# airball_sensor_board_v7.net
KiCad netlist of a schematic drawn in EAGLE
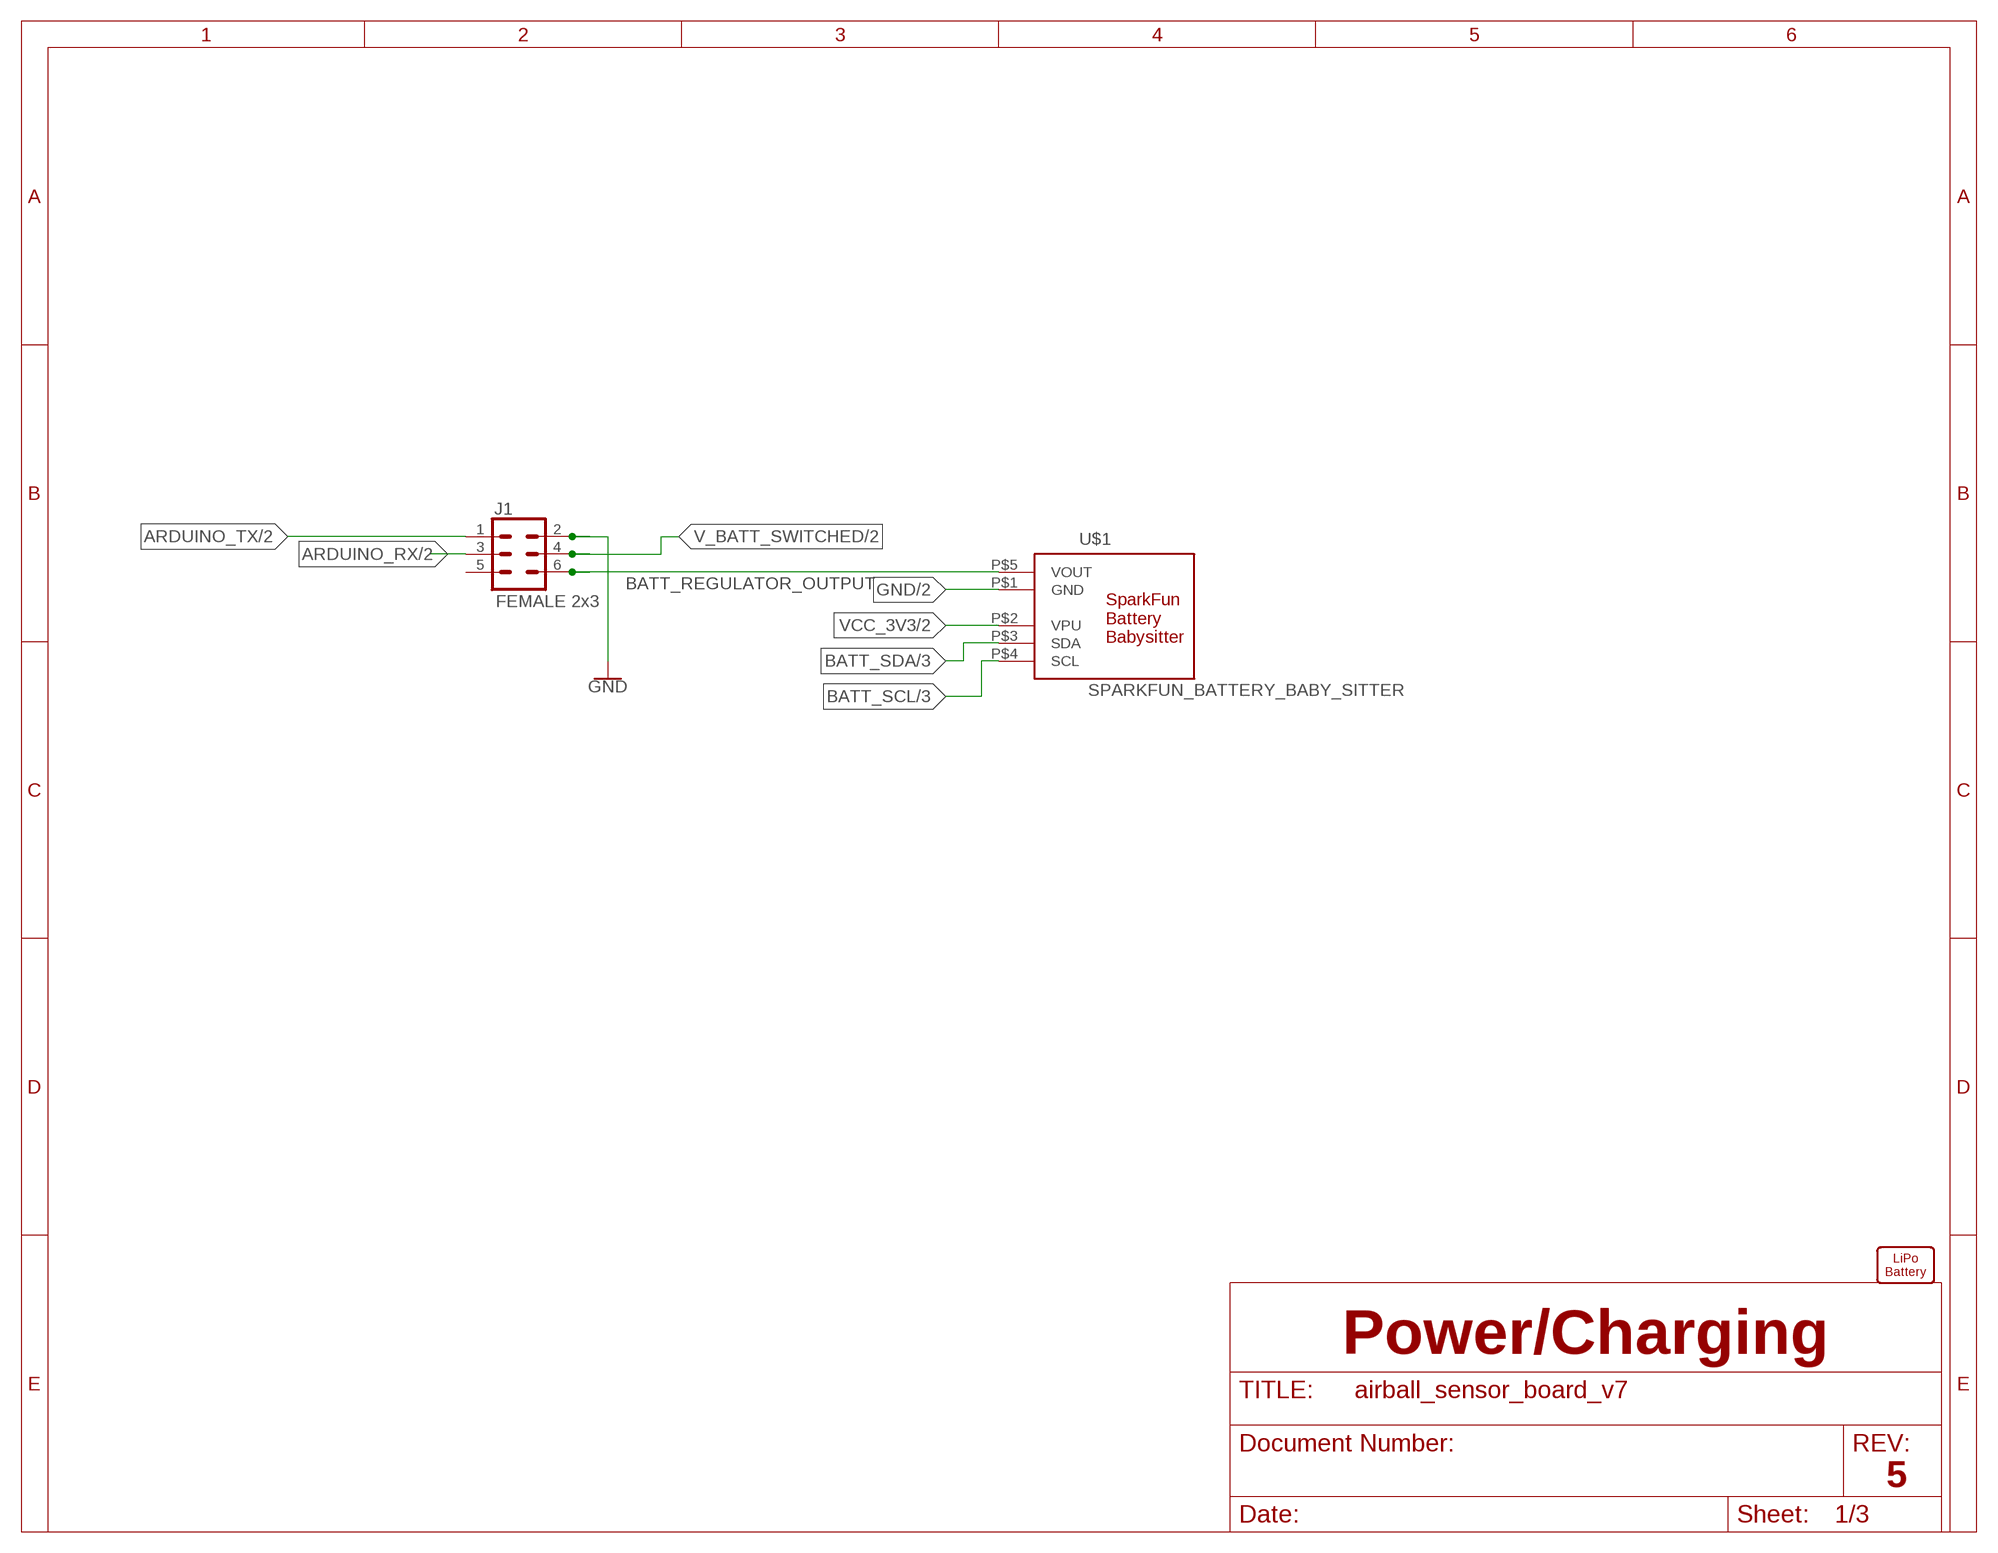
[diagram p0: schematic, sheet 1]
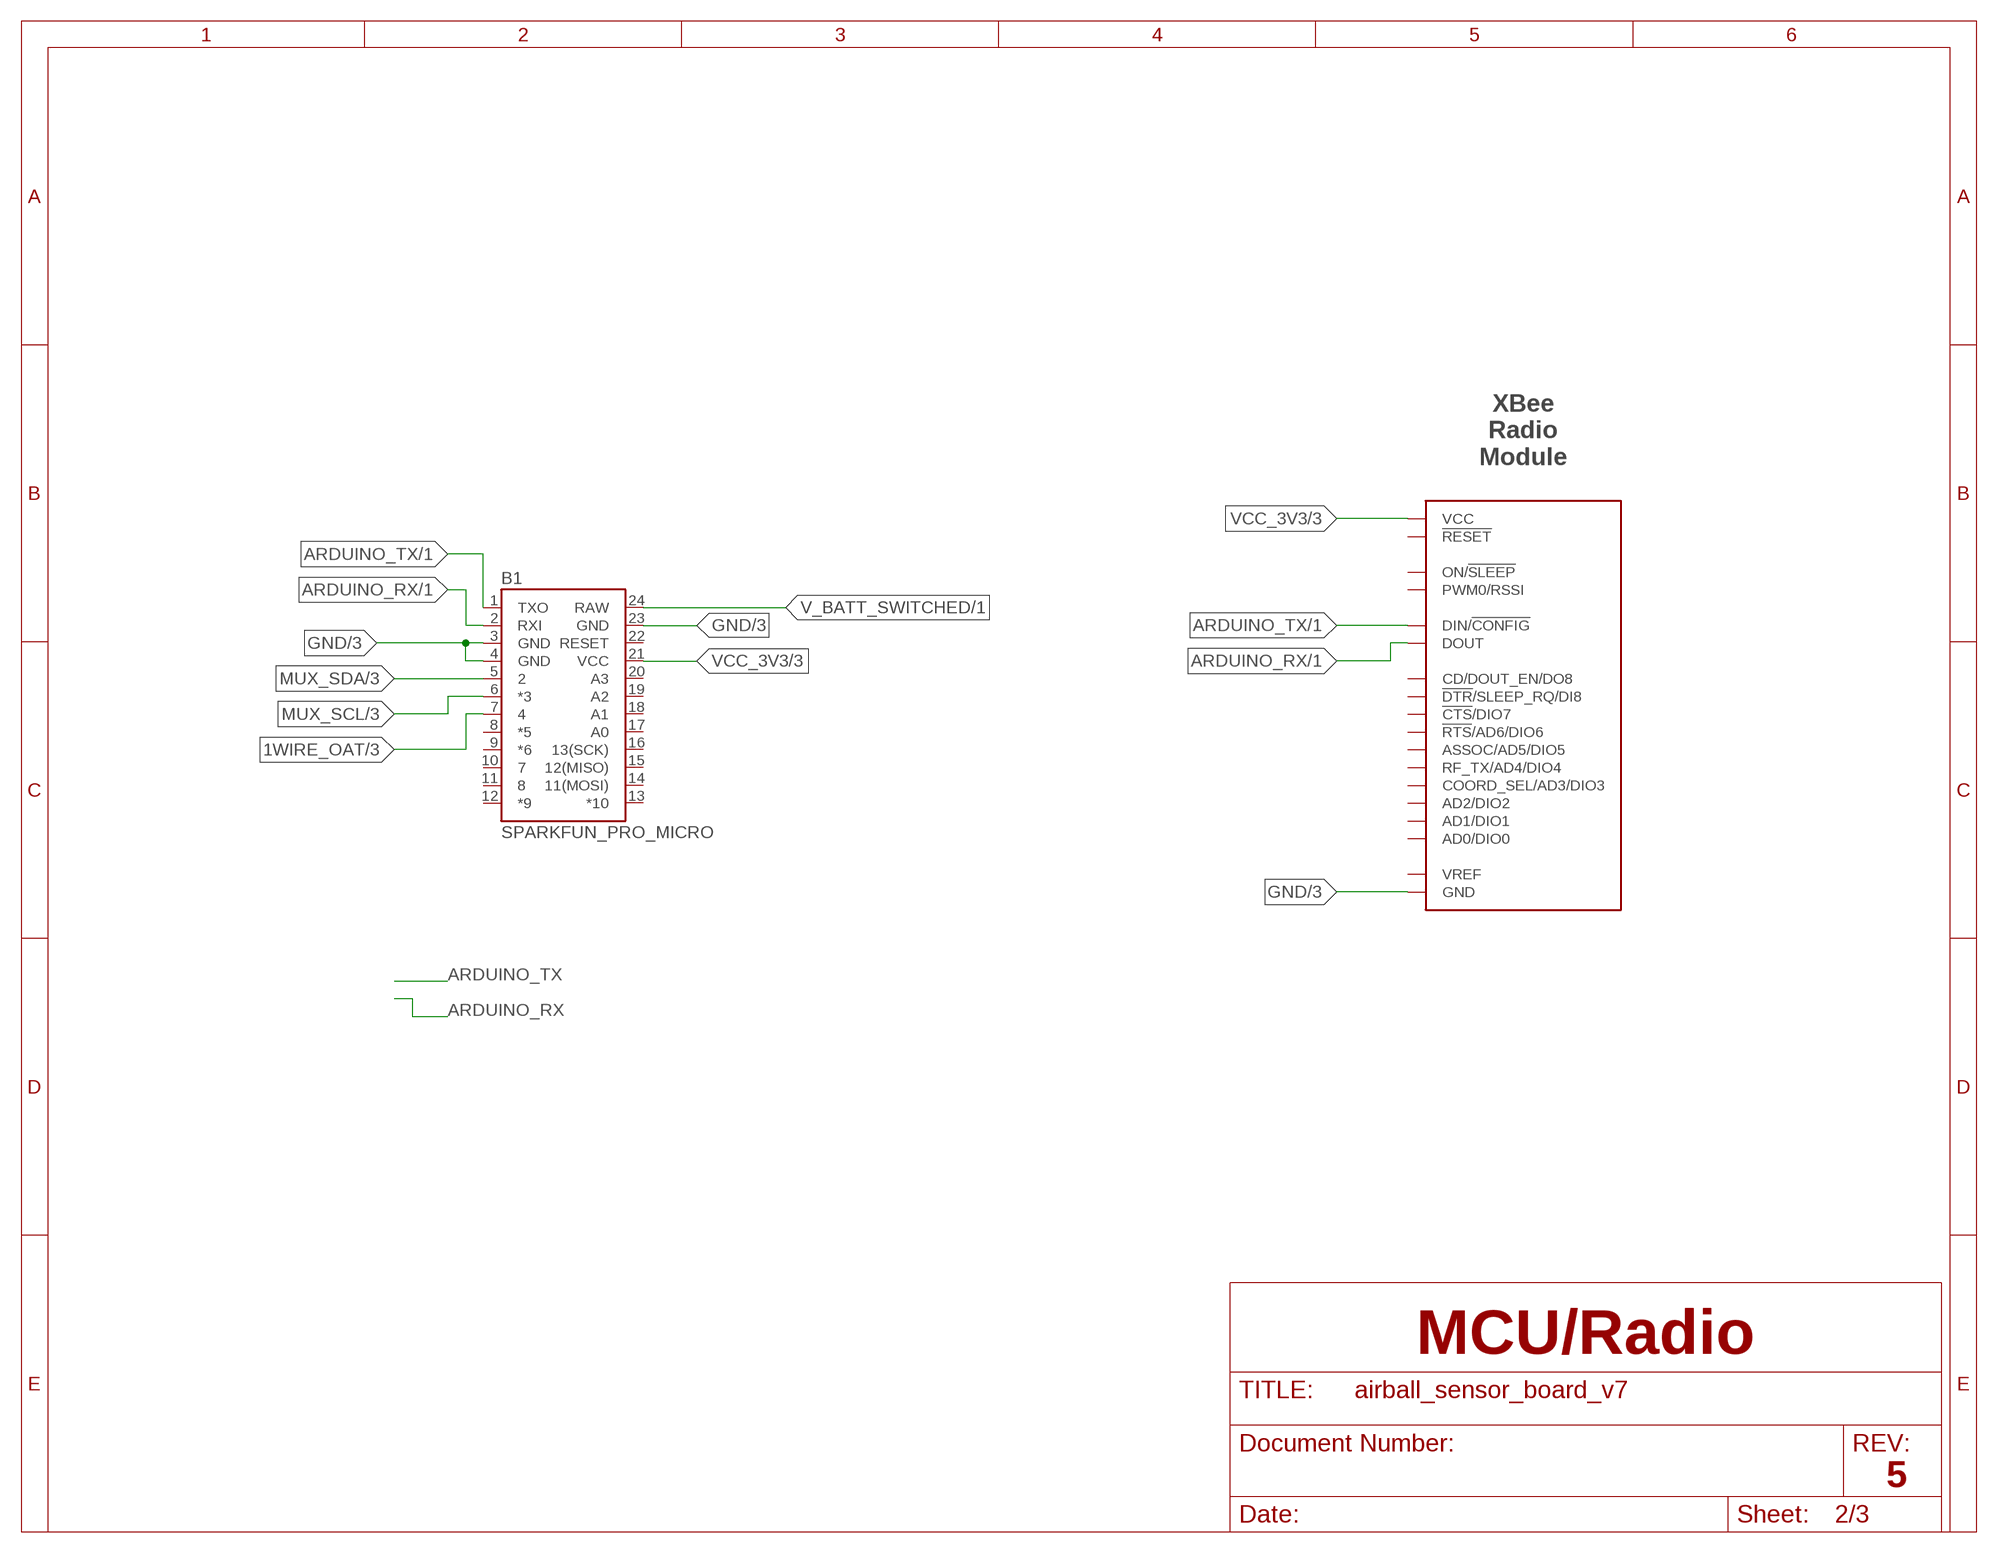
[diagram p1: schematic, sheet 2]
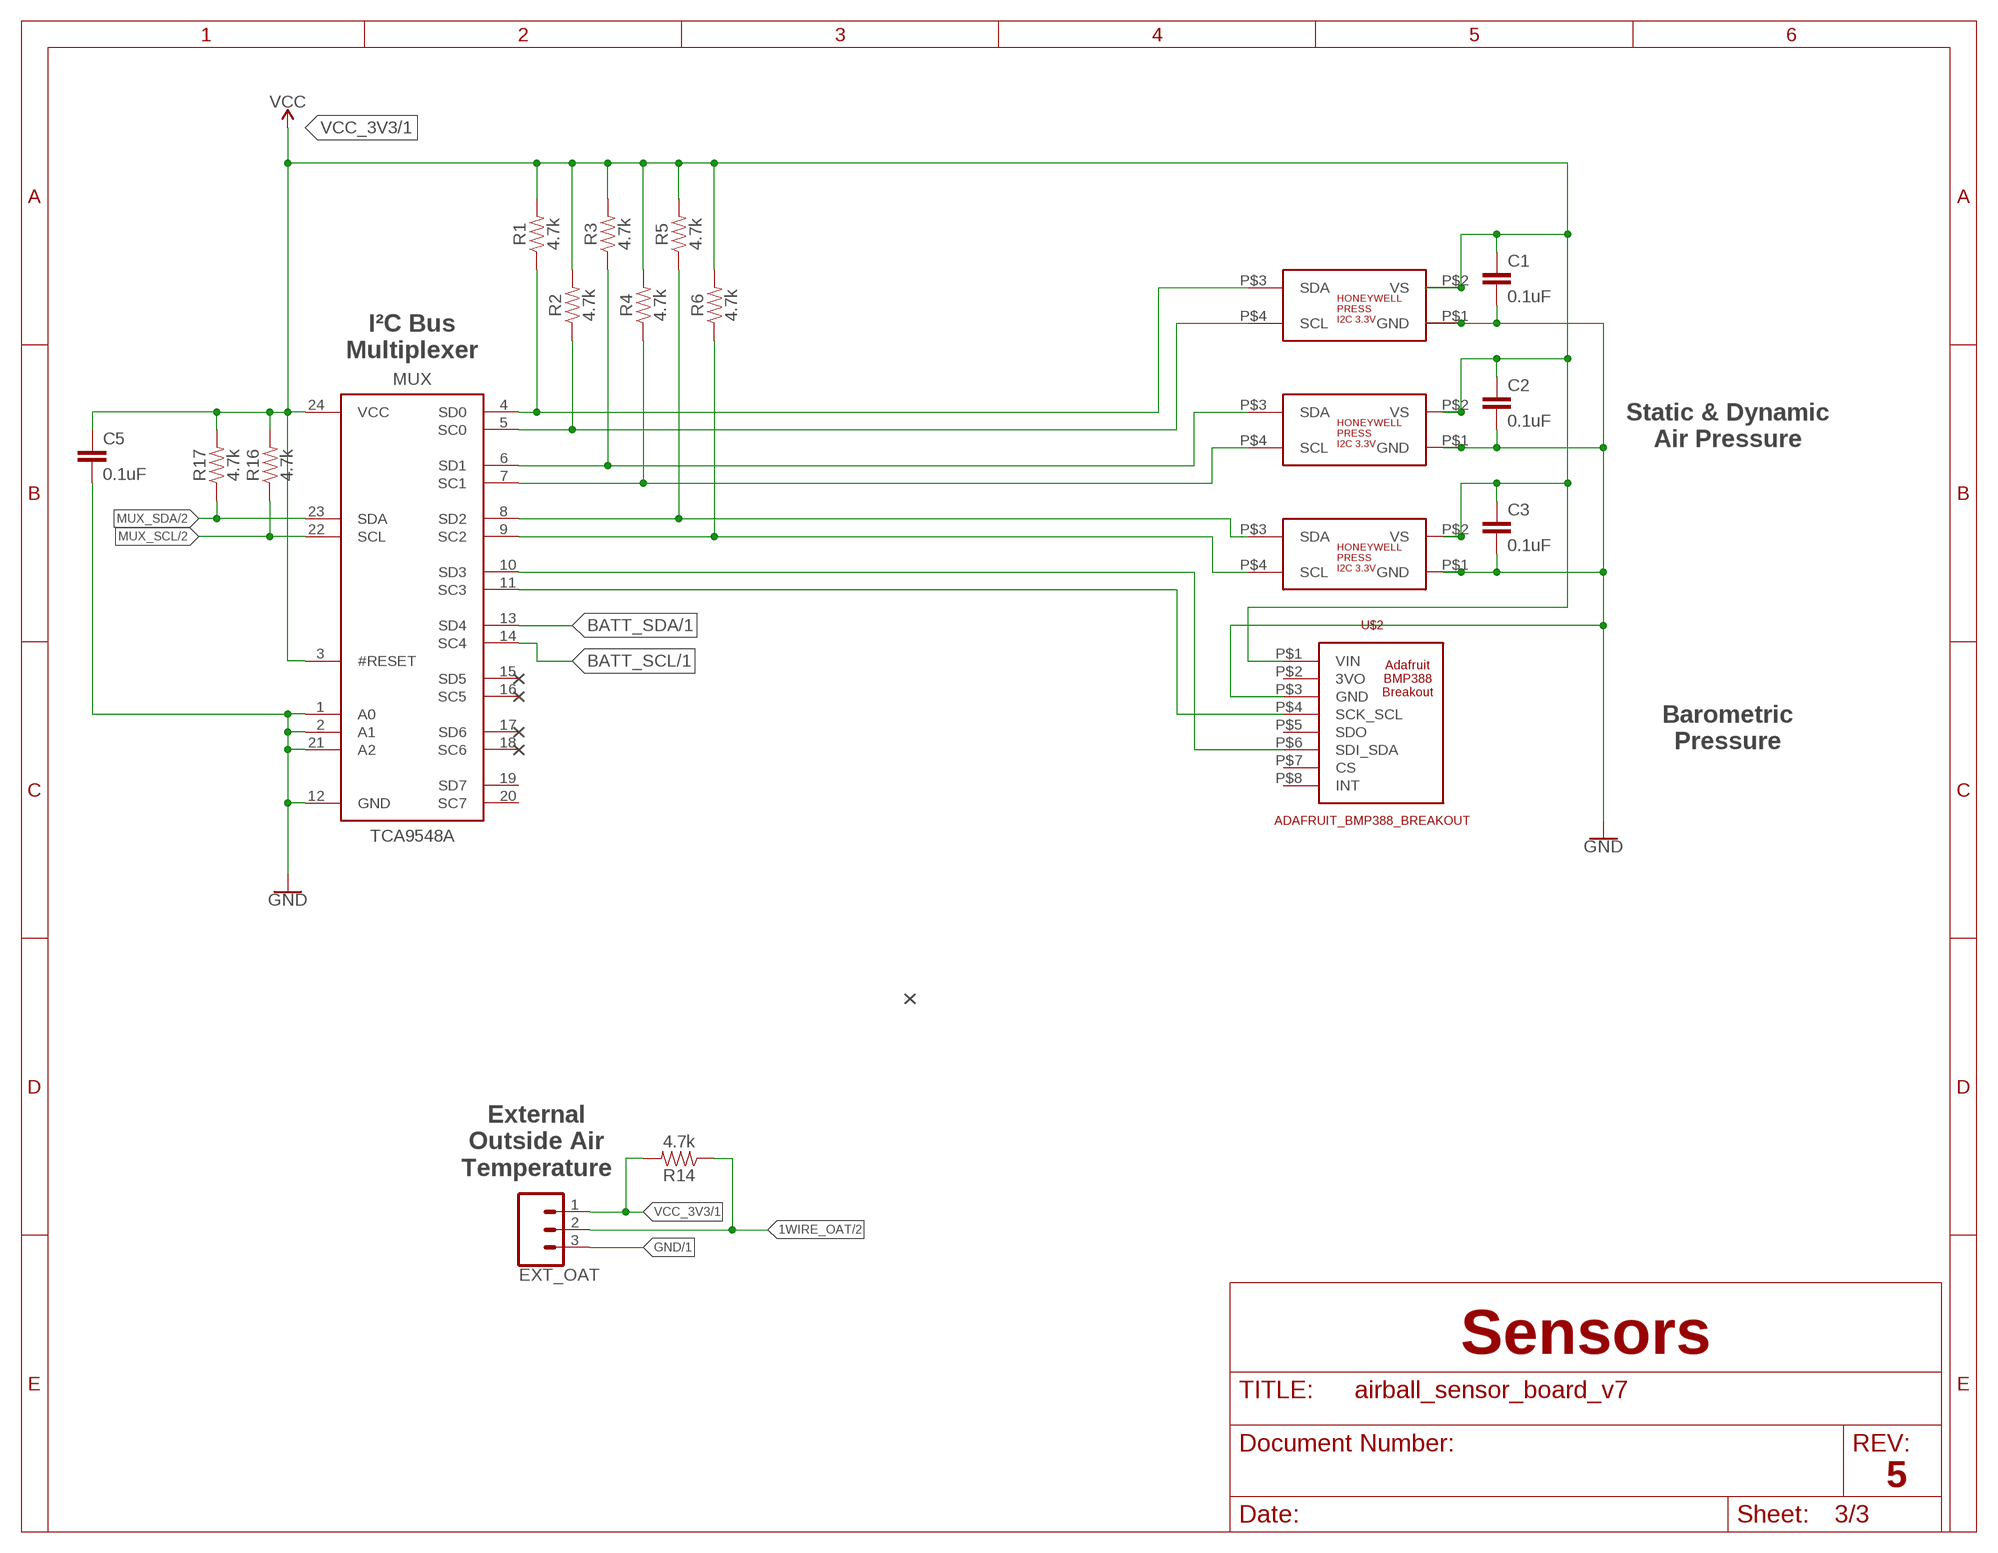
[diagram p2: schematic, sheet 3]

(export (version "E")
  (design (tool "Eeschema 10.0.6"))
  (components
    (comp (ref "C1")
      (value "0.1uF")
      (footprint "eagle-import:0603")
      (libsource (lib "eagle-import") (part "0.1UF-0603-25V-5%"))
    )
    (comp (ref "C2")
      (value "0.1uF")
      (footprint "eagle-import:0603")
      (libsource (lib "eagle-import") (part "0.1UF-0603-25V-5%"))
    )
    (comp (ref "C3")
      (value "0.1uF")
      (footprint "eagle-import:0603")
      (libsource (lib "eagle-import") (part "0.1UF-0603-25V-5%"))
    )
    (comp (ref "C5")
      (value "0.1uF")
      (footprint "eagle-import:0603")
      (libsource (lib "eagle-import") (part "0.1UF-0603-25V-5%"))
    )
    (comp (ref "DP0")
      (value "HONEYWELL_TRUSTABILITY_I2C_3.3V")
      (footprint "eagle-import:HONEYWELL_TRUSTABILITY_DIP_RR")
      (libsource (lib "eagle-import") (part "HONEYWELL_TRUSTABILITY_I2C_3.3V"))
    )
    (comp (ref "DPA")
      (value "HONEYWELL_TRUSTABILITY_I2C_3.3V")
      (footprint "eagle-import:HONEYWELL_TRUSTABILITY_DIP_RR")
      (libsource (lib "eagle-import") (part "HONEYWELL_TRUSTABILITY_I2C_3.3V"))
    )
    (comp (ref "DPB")
      (value "HONEYWELL_TRUSTABILITY_I2C_3.3V")
      (footprint "eagle-import:HONEYWELL_TRUSTABILITY_DIP_RR")
      (libsource (lib "eagle-import") (part "HONEYWELL_TRUSTABILITY_I2C_3.3V"))
    )
    (comp (ref "EXT_OAT")
      (value "CONN_03")
      (footprint "eagle-import:1X03")
      (libsource (lib "eagle-import") (part "CONN_03"))
    )
    (comp (ref "MUX")
      (value "TCA9548A")
      (footprint "eagle-import:TSSOP24")
      (libsource (lib "eagle-import") (part "TCA9548ATSSOP24"))
    )
    (comp (ref "R1")
      (value "4.7k")
      (footprint "eagle-import:0603")
      (libsource (lib "eagle-import") (part "4.7KOHM-0603-1/10W-1%"))
    )
    (comp (ref "R2")
      (value "4.7k")
      (footprint "eagle-import:0603")
      (libsource (lib "eagle-import") (part "4.7KOHM-0603-1/10W-1%"))
    )
    (comp (ref "R3")
      (value "4.7k")
      (footprint "eagle-import:0603")
      (libsource (lib "eagle-import") (part "4.7KOHM-0603-1/10W-1%"))
    )
    (comp (ref "R4")
      (value "4.7k")
      (footprint "eagle-import:0603")
      (libsource (lib "eagle-import") (part "4.7KOHM-0603-1/10W-1%"))
    )
    (comp (ref "R5")
      (value "4.7k")
      (footprint "eagle-import:0603")
      (libsource (lib "eagle-import") (part "4.7KOHM-0603-1/10W-1%"))
    )
    (comp (ref "R6")
      (value "4.7k")
      (footprint "eagle-import:0603")
      (libsource (lib "eagle-import") (part "4.7KOHM-0603-1/10W-1%"))
    )
    (comp (ref "R14")
      (value "4.7k")
      (footprint "eagle-import:0603")
      (libsource (lib "eagle-import") (part "4.7KOHM-0603-1/10W-1%"))
    )
    (comp (ref "R16")
      (value "4.7k")
      (footprint "eagle-import:0603")
      (libsource (lib "eagle-import") (part "4.7KOHM-0603-1/10W-1%"))
    )
    (comp (ref "R17")
      (value "4.7k")
      (footprint "eagle-import:0603")
      (libsource (lib "eagle-import") (part "4.7KOHM-0603-1/10W-1%"))
    )
    (comp (ref "U$2")
      (value "ADAFRUIT_BMP388_BREAKOUT")
      (footprint "eagle-import:ADAFRUIT_BMP388_BREAKOUT")
      (libsource (lib "eagle-import") (part "ADAFRUIT_BMP388_BREAKOUT"))
    )
    (comp (ref "J1")
      (value "FEMALE 2x3")
      (footprint "eagle-import:2X3")
      (libsource (lib "eagle-import") (part "CONN_03X2FEMALE"))
    )
    (comp (ref "U$1")
      (value "SPARKFUN_BATTERY_BABY_SITTER")
      (footprint "eagle-import:SPARKFUN_BATTERY_BABY_SITTER")
      (libsource (lib "eagle-import") (part "SPARKFUN_BATTERY_BABY_SITTER"))
    )
    (comp (ref "U$3")
      (value "LIPO_BATTERY_OUTLINE-1000MAH")
      (footprint "eagle-import:SPARKFUN_LIPO_1000MAH")
      (libsource (lib "eagle-import") (part "LIPO_BATTERY_OUTLINE-1000MAH"))
    )
    (comp (ref "B1")
      (value "SPARKFUN_PRO_MICRO")
      (footprint "eagle-import:SPARKFUN_PRO_MICRO")
      (libsource (lib "eagle-import") (part "SPARKFUN_PRO_MICRO"))
    )
    (comp (ref "XBEE")
      (value "XBEE-PRO-SMD")
      (footprint "eagle-import:XBEE-PRO-SMD")
      (libsource (lib "eagle-import") (part "XBEE-PRO-SMD"))
    )
  )
  (nets
    (net (code "1") (name "1WIRE_OAT") (class "Default")
      (node (ref "B1") (pin "7") (pinfunction "4_7") (pintype "bidirectional"))
      (node (ref "EXT_OAT") (pin "2") (pinfunction "2_2") (pintype "passive"))
      (node (ref "R14") (pin "1") (pinfunction "1_1") (pintype "passive"))
    )
    (net (code "2") (name "ARDUINO_RX") (class "Default")
      (node (ref "B1") (pin "2") (pinfunction "RXI_2") (pintype "bidirectional"))
      (node (ref "J1") (pin "3") (pinfunction "3_3") (pintype "bidirectional"))
      (node (ref "XBEE") (pin "2") (pinfunction "DOUT_2") (pintype "output"))
    )
    (net (code "3") (name "ARDUINO_TX") (class "Default")
      (node (ref "B1") (pin "1") (pinfunction "TXO_1") (pintype "bidirectional"))
      (node (ref "J1") (pin "1") (pinfunction "1_1") (pintype "bidirectional"))
      (node (ref "XBEE") (pin "3") (pinfunction "DIN/~{CONFIG}_3") (pintype "input"))
    )
    (net (code "4") (name "BATT_REGULATOR_OUTPUT") (class "Default")
      (node (ref "J1") (pin "6") (pinfunction "6_6") (pintype "bidirectional"))
      (node (ref "U$1") (pin "P$5") (pinfunction "VOUT_P$5") (pintype "bidirectional"))
    )
    (net (code "5") (name "BATT_SCL") (class "Default")
      (node (ref "MUX") (pin "14") (pinfunction "SC4_14") (pintype "bidirectional"))
      (node (ref "U$1") (pin "P$4") (pinfunction "SCL_P$4") (pintype "bidirectional"))
    )
    (net (code "6") (name "BATT_SDA") (class "Default")
      (node (ref "MUX") (pin "13") (pinfunction "SD4_13") (pintype "bidirectional"))
      (node (ref "U$1") (pin "P$3") (pinfunction "SDA_P$3") (pintype "bidirectional"))
    )
    (net (code "7") (name "GND") (class "Default")
      (node (ref "B1") (pin "23") (pinfunction "GND_23") (pintype "power_in"))
      (node (ref "B1") (pin "3") (pinfunction "GND_3") (pintype "power_in"))
      (node (ref "B1") (pin "4") (pinfunction "GND_4") (pintype "power_in"))
      (node (ref "C1") (pin "2") (pinfunction "2_2") (pintype "passive"))
      (node (ref "C2") (pin "2") (pinfunction "2_2") (pintype "passive"))
      (node (ref "C3") (pin "2") (pinfunction "2_2") (pintype "passive"))
      (node (ref "C5") (pin "2") (pinfunction "2_2") (pintype "passive"))
      (node (ref "DP0") (pin "P$1") (pinfunction "GND_P$1") (pintype "bidirectional"))
      (node (ref "DPA") (pin "P$1") (pinfunction "GND_P$1") (pintype "bidirectional"))
      (node (ref "DPB") (pin "P$1") (pinfunction "GND_P$1") (pintype "bidirectional"))
      (node (ref "EXT_OAT") (pin "3") (pinfunction "3_3") (pintype "passive"))
      (node (ref "J1") (pin "2") (pinfunction "2_2") (pintype "bidirectional"))
      (node (ref "MUX") (pin "1") (pinfunction "A0_1") (pintype "bidirectional"))
      (node (ref "MUX") (pin "12") (pinfunction "GND_12") (pintype "bidirectional"))
      (node (ref "MUX") (pin "2") (pinfunction "A1_2") (pintype "bidirectional"))
      (node (ref "MUX") (pin "21") (pinfunction "A2_21") (pintype "bidirectional"))
      (node (ref "U$1") (pin "P$1") (pinfunction "GND_P$1") (pintype "bidirectional"))
      (node (ref "U$2") (pin "P$3") (pinfunction "GND_P$3") (pintype "bidirectional"))
      (node (ref "XBEE") (pin "10") (pinfunction "GND_10") (pintype "power_in"))
    )
    (net (code "8") (name "MUX_SCL") (class "Default")
      (node (ref "B1") (pin "6") (pinfunction "*3_6") (pintype "bidirectional"))
      (node (ref "MUX") (pin "22") (pinfunction "SCL_22") (pintype "bidirectional"))
      (node (ref "R16") (pin "1") (pinfunction "1_1") (pintype "passive"))
    )
    (net (code "9") (name "MUX_SDA") (class "Default")
      (node (ref "B1") (pin "5") (pinfunction "2_5") (pintype "bidirectional"))
      (node (ref "MUX") (pin "23") (pinfunction "SDA_23") (pintype "bidirectional"))
      (node (ref "R17") (pin "1") (pinfunction "1_1") (pintype "passive"))
    )
    (net (code "10") (name "Net-(DP0-SCL)") (class "Default")
      (node (ref "DP0") (pin "P$4") (pinfunction "SCL_P$4") (pintype "bidirectional"))
      (node (ref "MUX") (pin "5") (pinfunction "SC0_5") (pintype "bidirectional"))
      (node (ref "R2") (pin "1") (pinfunction "1_1") (pintype "passive"))
    )
    (net (code "11") (name "Net-(DP0-SDA)") (class "Default")
      (node (ref "DP0") (pin "P$3") (pinfunction "SDA_P$3") (pintype "bidirectional"))
      (node (ref "MUX") (pin "4") (pinfunction "SD0_4") (pintype "bidirectional"))
      (node (ref "R1") (pin "1") (pinfunction "1_1") (pintype "passive"))
    )
    (net (code "12") (name "Net-(DPA-SCL)") (class "Default")
      (node (ref "DPA") (pin "P$4") (pinfunction "SCL_P$4") (pintype "bidirectional"))
      (node (ref "MUX") (pin "7") (pinfunction "SC1_7") (pintype "bidirectional"))
      (node (ref "R4") (pin "1") (pinfunction "1_1") (pintype "passive"))
    )
    (net (code "13") (name "Net-(DPA-SDA)") (class "Default")
      (node (ref "DPA") (pin "P$3") (pinfunction "SDA_P$3") (pintype "bidirectional"))
      (node (ref "MUX") (pin "6") (pinfunction "SD1_6") (pintype "bidirectional"))
      (node (ref "R3") (pin "1") (pinfunction "1_1") (pintype "passive"))
    )
    (net (code "14") (name "Net-(DPB-SCL)") (class "Default")
      (node (ref "DPB") (pin "P$4") (pinfunction "SCL_P$4") (pintype "bidirectional"))
      (node (ref "MUX") (pin "9") (pinfunction "SC2_9") (pintype "bidirectional"))
      (node (ref "R6") (pin "1") (pinfunction "1_1") (pintype "passive"))
    )
    (net (code "15") (name "Net-(DPB-SDA)") (class "Default")
      (node (ref "DPB") (pin "P$3") (pinfunction "SDA_P$3") (pintype "bidirectional"))
      (node (ref "MUX") (pin "8") (pinfunction "SD2_8") (pintype "bidirectional"))
      (node (ref "R5") (pin "1") (pinfunction "1_1") (pintype "passive"))
    )
    (net (code "16") (name "Net-(MUX-SC3)") (class "Default")
      (node (ref "MUX") (pin "11") (pinfunction "SC3_11") (pintype "bidirectional"))
      (node (ref "U$2") (pin "P$4") (pinfunction "SCK_SCL_P$4") (pintype "bidirectional"))
    )
    (net (code "17") (name "Net-(MUX-SD3)") (class "Default")
      (node (ref "MUX") (pin "10") (pinfunction "SD3_10") (pintype "bidirectional"))
      (node (ref "U$2") (pin "P$6") (pinfunction "SDI_SDA_P$6") (pintype "bidirectional"))
    )
    (net (code "18") (name "VCC_3V3") (class "Default")
      (node (ref "B1") (pin "21") (pinfunction "VCC_21") (pintype "power_in"))
      (node (ref "C1") (pin "1") (pinfunction "1_1") (pintype "passive"))
      (node (ref "C2") (pin "1") (pinfunction "1_1") (pintype "passive"))
      (node (ref "C3") (pin "1") (pinfunction "1_1") (pintype "passive"))
      (node (ref "C5") (pin "1") (pinfunction "1_1") (pintype "passive"))
      (node (ref "DP0") (pin "P$2") (pinfunction "VS_P$2") (pintype "bidirectional"))
      (node (ref "DPA") (pin "P$2") (pinfunction "VS_P$2") (pintype "bidirectional"))
      (node (ref "DPB") (pin "P$2") (pinfunction "VS_P$2") (pintype "bidirectional"))
      (node (ref "EXT_OAT") (pin "1") (pinfunction "1_1") (pintype "passive"))
      (node (ref "MUX") (pin "24") (pinfunction "VCC_24") (pintype "bidirectional"))
      (node (ref "MUX") (pin "3") (pinfunction "#RESET_3") (pintype "bidirectional"))
      (node (ref "R1") (pin "2") (pinfunction "2_2") (pintype "passive"))
      (node (ref "R14") (pin "2") (pinfunction "2_2") (pintype "passive"))
      (node (ref "R16") (pin "2") (pinfunction "2_2") (pintype "passive"))
      (node (ref "R17") (pin "2") (pinfunction "2_2") (pintype "passive"))
      (node (ref "R2") (pin "2") (pinfunction "2_2") (pintype "passive"))
      (node (ref "R3") (pin "2") (pinfunction "2_2") (pintype "passive"))
      (node (ref "R4") (pin "2") (pinfunction "2_2") (pintype "passive"))
      (node (ref "R5") (pin "2") (pinfunction "2_2") (pintype "passive"))
      (node (ref "R6") (pin "2") (pinfunction "2_2") (pintype "passive"))
      (node (ref "U$1") (pin "P$2") (pinfunction "VPU_P$2") (pintype "bidirectional"))
      (node (ref "U$2") (pin "P$1") (pinfunction "VIN_P$1") (pintype "bidirectional"))
      (node (ref "XBEE") (pin "1") (pinfunction "VCC_1") (pintype "power_in"))
    )
    (net (code "19") (name "V_BATT_SWITCHED") (class "Default")
      (node (ref "B1") (pin "24") (pinfunction "RAW_24") (pintype "power_in"))
      (node (ref "J1") (pin "4") (pinfunction "4_4") (pintype "bidirectional"))
    )
    (net (code "20") (name "unconnected-(B1-*5-Pad8)") (class "Default")
      (node (ref "B1") (pin "8") (pinfunction "*5_8") (pintype "bidirectional"))
    )
    (net (code "21") (name "unconnected-(B1-*6-Pad9)") (class "Default")
      (node (ref "B1") (pin "9") (pinfunction "*6_9") (pintype "bidirectional"))
    )
    (net (code "22") (name "unconnected-(B1-*9-Pad12)") (class "Default")
      (node (ref "B1") (pin "12") (pinfunction "*9_12") (pintype "bidirectional"))
    )
    (net (code "23") (name "unconnected-(B1-*10-Pad13)") (class "Default")
      (node (ref "B1") (pin "13") (pinfunction "*10_13") (pintype "bidirectional"))
    )
    (net (code "24") (name "unconnected-(B1-7-Pad10)") (class "Default")
      (node (ref "B1") (pin "10") (pinfunction "7_10") (pintype "bidirectional"))
    )
    (net (code "25") (name "unconnected-(B1-8-Pad11)") (class "Default")
      (node (ref "B1") (pin "11") (pinfunction "8_11") (pintype "bidirectional"))
    )
    (net (code "26") (name "unconnected-(B1-11(MOSI)-Pad14)") (class "Default")
      (node (ref "B1") (pin "14") (pinfunction "11(MOSI)_14") (pintype "bidirectional"))
    )
    (net (code "27") (name "unconnected-(B1-12(MISO)-Pad15)") (class "Default")
      (node (ref "B1") (pin "15") (pinfunction "12(MISO)_15") (pintype "bidirectional"))
    )
    (net (code "28") (name "unconnected-(B1-13(SCK)-Pad16)") (class "Default")
      (node (ref "B1") (pin "16") (pinfunction "13(SCK)_16") (pintype "bidirectional"))
    )
    (net (code "29") (name "unconnected-(B1-A0-Pad17)") (class "Default")
      (node (ref "B1") (pin "17") (pinfunction "A0_17") (pintype "bidirectional"))
    )
    (net (code "30") (name "unconnected-(B1-A1-Pad18)") (class "Default")
      (node (ref "B1") (pin "18") (pinfunction "A1_18") (pintype "bidirectional"))
    )
    (net (code "31") (name "unconnected-(B1-A2-Pad19)") (class "Default")
      (node (ref "B1") (pin "19") (pinfunction "A2_19") (pintype "bidirectional"))
    )
    (net (code "32") (name "unconnected-(B1-A3-Pad20)") (class "Default")
      (node (ref "B1") (pin "20") (pinfunction "A3_20") (pintype "bidirectional"))
    )
    (net (code "33") (name "unconnected-(B1-RESET-Pad22)") (class "Default")
      (node (ref "B1") (pin "22") (pinfunction "RESET_22") (pintype "bidirectional"))
    )
    (net (code "34") (name "unconnected-(J1-Pad5)") (class "Default")
      (node (ref "J1") (pin "5") (pinfunction "5_5") (pintype "bidirectional"))
    )
    (net (code "35") (name "unconnected-(MUX-SC5-Pad16)") (class "Default")
      (node (ref "MUX") (pin "16") (pinfunction "SC5_16") (pintype "bidirectional"))
    )
    (net (code "36") (name "unconnected-(MUX-SC6-Pad18)") (class "Default")
      (node (ref "MUX") (pin "18") (pinfunction "SC6_18") (pintype "bidirectional"))
    )
    (net (code "37") (name "unconnected-(MUX-SC7-Pad20)") (class "Default")
      (node (ref "MUX") (pin "20") (pinfunction "SC7_20") (pintype "bidirectional"))
    )
    (net (code "38") (name "unconnected-(MUX-SD5-Pad15)") (class "Default")
      (node (ref "MUX") (pin "15") (pinfunction "SD5_15") (pintype "bidirectional"))
    )
    (net (code "39") (name "unconnected-(MUX-SD6-Pad17)") (class "Default")
      (node (ref "MUX") (pin "17") (pinfunction "SD6_17") (pintype "bidirectional"))
    )
    (net (code "40") (name "unconnected-(MUX-SD7-Pad19)") (class "Default")
      (node (ref "MUX") (pin "19") (pinfunction "SD7_19") (pintype "bidirectional"))
    )
    (net (code "41") (name "unconnected-(U$2-3VO-PadP$2)") (class "Default")
      (node (ref "U$2") (pin "P$2") (pinfunction "3VO_P$2") (pintype "bidirectional"))
    )
    (net (code "42") (name "unconnected-(U$2-CS-PadP$7)") (class "Default")
      (node (ref "U$2") (pin "P$7") (pinfunction "CS_P$7") (pintype "bidirectional"))
    )
    (net (code "43") (name "unconnected-(U$2-INT-PadP$8)") (class "Default")
      (node (ref "U$2") (pin "P$8") (pinfunction "INT_P$8") (pintype "bidirectional"))
    )
    (net (code "44") (name "unconnected-(U$2-SDO-PadP$5)") (class "Default")
      (node (ref "U$2") (pin "P$5") (pinfunction "SDO_P$5") (pintype "bidirectional"))
    )
    (net (code "45") (name "unconnected-(XBEE-AD0{slash}DIO0-Pad20)") (class "Default")
      (node (ref "XBEE") (pin "20") (pinfunction "AD0/DIO0_20") (pintype "bidirectional"))
    )
    (net (code "46") (name "unconnected-(XBEE-AD1{slash}DIO1-Pad19)") (class "Default")
      (node (ref "XBEE") (pin "19") (pinfunction "AD1/DIO1_19") (pintype "bidirectional"))
    )
    (net (code "47") (name "unconnected-(XBEE-AD2{slash}DIO2-Pad18)") (class "Default")
      (node (ref "XBEE") (pin "18") (pinfunction "AD2/DIO2_18") (pintype "bidirectional"))
    )
    (net (code "48") (name "unconnected-(XBEE-ASSOC{slash}AD5{slash}DIO5-Pad15)") (class "Default")
      (node (ref "XBEE") (pin "15") (pinfunction "ASSOC/AD5/DIO5_15") (pintype "bidirectional"))
    )
    (net (code "49") (name "unconnected-(XBEE-CD{slash}DOUT_EN{slash}DO8-Pad4)") (class "Default")
      (node (ref "XBEE") (pin "4") (pinfunction "CD/DOUT_EN/DO8_4") (pintype "output"))
    )
    (net (code "50") (name "unconnected-(XBEE-COORD_SEL{slash}AD3{slash}DIO3-Pad17)") (class "Default")
      (node (ref "XBEE") (pin "17") (pinfunction "COORD_SEL/AD3/DIO3_17") (pintype "bidirectional"))
    )
    (net (code "51") (name "unconnected-(XBEE-ON{slash}~{SLEEP}-Pad13)") (class "Default")
      (node (ref "XBEE") (pin "13") (pinfunction "ON/~{SLEEP}_13") (pintype "output"))
    )
    (net (code "52") (name "unconnected-(XBEE-PWM0{slash}RSSI-Pad6)") (class "Default")
      (node (ref "XBEE") (pin "6") (pinfunction "PWM0/RSSI_6") (pintype "output"))
    )
    (net (code "53") (name "unconnected-(XBEE-RF_TX{slash}AD4{slash}DIO4-Pad11)") (class "Default")
      (node (ref "XBEE") (pin "11") (pinfunction "RF_TX/AD4/DIO4_11") (pintype "bidirectional"))
    )
    (net (code "54") (name "unconnected-(XBEE-VREF-Pad14)") (class "Default")
      (node (ref "XBEE") (pin "14") (pinfunction "VREF_14") (pintype "input"))
    )
    (net (code "55") (name "unconnected-(XBEE-~{CTS}{slash}DIO7-Pad12)") (class "Default")
      (node (ref "XBEE") (pin "12") (pinfunction "~{CTS}/DIO7_12") (pintype "bidirectional"))
    )
    (net (code "56") (name "unconnected-(XBEE-~{DTR}{slash}SLEEP_RQ{slash}DI8-Pad9)") (class "Default")
      (node (ref "XBEE") (pin "9") (pinfunction "~{DTR}/SLEEP_RQ/DI8_9") (pintype "bidirectional"))
    )
    (net (code "57") (name "unconnected-(XBEE-~{RESET}-Pad5)") (class "Default")
      (node (ref "XBEE") (pin "5") (pinfunction "~{RESET}_5") (pintype "input"))
    )
    (net (code "58") (name "unconnected-(XBEE-~{RTS}{slash}AD6{slash}DIO6-Pad16)") (class "Default")
      (node (ref "XBEE") (pin "16") (pinfunction "~{RTS}/AD6/DIO6_16") (pintype "bidirectional"))
    )
  )
)
